# DAC_GainOutputStage2.net
KiCad netlist of a schematic drawn in EAGLE
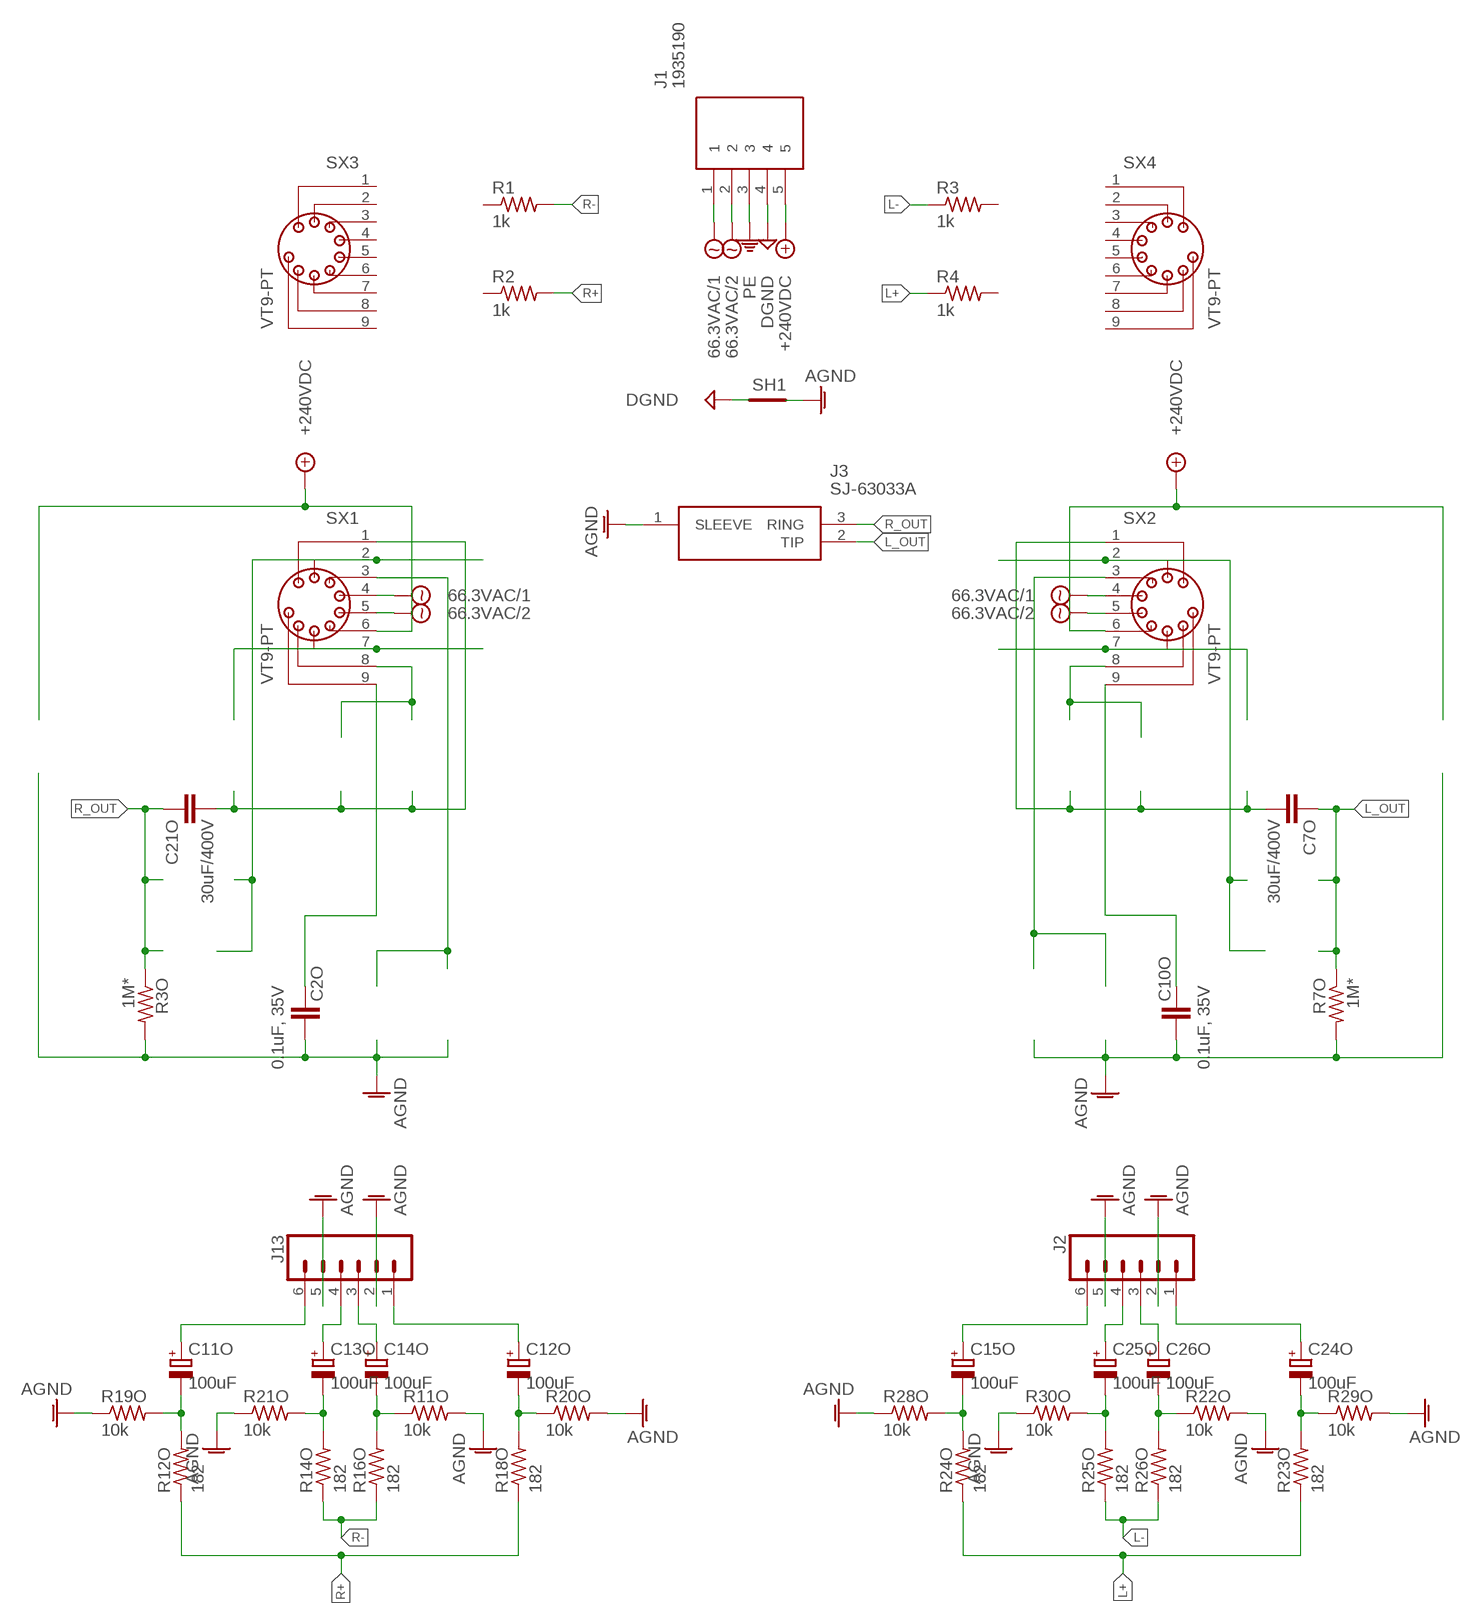
[diagram p0: schematic, sheet 1]

(export (version "E")
  (design (tool "Eeschema 10.0.6"))
  (components
    (comp (ref "C2O")
      (value "0.1uF, 35V")
      (footprint "eagle-import:MKS4B031002A00JC00")
      (fields
        (field (name "MANUFACTURER_PART_NUMBER") "MKS4B031002A00JC00")
        (field (name "MOUSER_PART_NUMBER") "505-MKS4B0312AJC")
      )
      (libsource (lib "eagle-import") (part "MKS4B031002A00JC00"))
    )
    (comp (ref "C7O")
      (value "30uF/400V")
      (footprint "eagle-import:DCP4G053006ID2KSSD")
      (fields
        (field (name "MANUFACTURER_PART_NUMBER") "DCP4G053006ID2KSSD")
        (field (name "MOUSER_PART_NUMBER") "505-DCP4G0536ID2KSSD")
      )
      (libsource (lib "eagle-import") (part "DCP4G053006ID2KSSD"))
    )
    (comp (ref "C10O")
      (value "0.1uF, 35V")
      (footprint "eagle-import:MKS4B031002A00JC00")
      (fields
        (field (name "MANUFACTURER_PART_NUMBER") "MKS4B031002A00JC00")
        (field (name "MOUSER_PART_NUMBER") "505-MKS4B0312AJC")
      )
      (libsource (lib "eagle-import") (part "MKS4B031002A00JC00"))
    )
    (comp (ref "C11O")
      (value "100uF")
      (footprint "eagle-import:CAPPRD350W60D825H1300")
      (fields
        (field (name "ARROW_PART_NUMBER") "UFW1H101MPD1TD")
        (field (name "MOUSER_PART_NUMBER") "647-UFW1H101MPD1TD")
      )
      (libsource (lib "eagle-import") (part "UFW1H101MPD1TD"))
    )
    (comp (ref "C12O")
      (value "100uF")
      (footprint "eagle-import:CAPPRD350W60D825H1300")
      (fields
        (field (name "ARROW_PART_NUMBER") "UFW1H101MPD1TD")
        (field (name "MOUSER_PART_NUMBER") "647-UFW1H101MPD1TD")
      )
      (libsource (lib "eagle-import") (part "UFW1H101MPD1TD"))
    )
    (comp (ref "C13O")
      (value "100uF")
      (footprint "eagle-import:CAPPRD350W60D825H1300")
      (fields
        (field (name "ARROW_PART_NUMBER") "UFW1H101MPD1TD")
        (field (name "MOUSER_PART_NUMBER") "647-UFW1H101MPD1TD")
      )
      (libsource (lib "eagle-import") (part "UFW1H101MPD1TD"))
    )
    (comp (ref "C14O")
      (value "100uF")
      (footprint "eagle-import:CAPPRD350W60D825H1300")
      (fields
        (field (name "ARROW_PART_NUMBER") "UFW1H101MPD1TD")
        (field (name "MOUSER_PART_NUMBER") "647-UFW1H101MPD1TD")
      )
      (libsource (lib "eagle-import") (part "UFW1H101MPD1TD"))
    )
    (comp (ref "C15O")
      (value "100uF")
      (footprint "eagle-import:CAPPRD350W60D825H1300")
      (fields
        (field (name "ARROW_PART_NUMBER") "UFW1H101MPD1TD")
        (field (name "MOUSER_PART_NUMBER") "647-UFW1H101MPD1TD")
      )
      (libsource (lib "eagle-import") (part "UFW1H101MPD1TD"))
    )
    (comp (ref "C21O")
      (value "30uF/400V")
      (footprint "eagle-import:DCP4G053006ID2KSSD")
      (fields
        (field (name "MANUFACTURER_PART_NUMBER") "DCP4G053006ID2KSSD")
        (field (name "MOUSER_PART_NUMBER") "505-DCP4G0536ID2KSSD")
      )
      (libsource (lib "eagle-import") (part "DCP4G053006ID2KSSD"))
    )
    (comp (ref "C24O")
      (value "100uF")
      (footprint "eagle-import:CAPPRD350W60D825H1300")
      (fields
        (field (name "ARROW_PART_NUMBER") "UFW1H101MPD1TD")
        (field (name "MOUSER_PART_NUMBER") "647-UFW1H101MPD1TD")
      )
      (libsource (lib "eagle-import") (part "UFW1H101MPD1TD"))
    )
    (comp (ref "C25O")
      (value "100uF")
      (footprint "eagle-import:CAPPRD350W60D825H1300")
      (fields
        (field (name "ARROW_PART_NUMBER") "UFW1H101MPD1TD")
        (field (name "MOUSER_PART_NUMBER") "647-UFW1H101MPD1TD")
      )
      (libsource (lib "eagle-import") (part "UFW1H101MPD1TD"))
    )
    (comp (ref "C26O")
      (value "100uF")
      (footprint "eagle-import:CAPPRD350W60D825H1300")
      (fields
        (field (name "ARROW_PART_NUMBER") "UFW1H101MPD1TD")
        (field (name "MOUSER_PART_NUMBER") "647-UFW1H101MPD1TD")
      )
      (libsource (lib "eagle-import") (part "UFW1H101MPD1TD"))
    )
    (comp (ref "J1")
      (value "1935190")
      (footprint "eagle-import:1935190")
      (fields (field (name "MOUSER_PART_NUMBER") "651-1935190"))
      (libsource (lib "eagle-import") (part "1935190"))
    )
    (comp (ref "J2")
      (value "CONN_06SILK_FEMALE_PTH")
      (footprint "eagle-import:1X06")
      (libsource (lib "eagle-import") (part "CONN_06SILK_FEMALE_PTH"))
    )
    (comp (ref "J3")
      (value "SJ-63033A")
      (footprint "eagle-import:SJ63033A")
      (libsource (lib "eagle-import") (part "SJ-63033A"))
    )
    (comp (ref "J13")
      (value "CONN_06SILK_FEMALE_PTH")
      (footprint "eagle-import:1X06")
      (libsource (lib "eagle-import") (part "CONN_06SILK_FEMALE_PTH"))
    )
    (comp (ref "R1")
      (value "1k")
      (footprint "eagle-import:0207_10")
      (libsource (lib "eagle-import") (part "R-US_0207/10"))
    )
    (comp (ref "R2")
      (value "1k")
      (footprint "eagle-import:0207_10")
      (libsource (lib "eagle-import") (part "R-US_0207/10"))
    )
    (comp (ref "R3")
      (value "1k")
      (footprint "eagle-import:0207_10")
      (libsource (lib "eagle-import") (part "R-US_0207/10"))
    )
    (comp (ref "R3O")
      (value "1M*")
      (footprint "eagle-import:RESAD1540W60L620D230")
      (fields
        (field (name "MANUFACTURER_PART_NUMBER") "LR1F1M0")
        (field (name "MOUSER_PART_NUMBER") "279-LR1F1M0")
      )
      (libsource (lib "eagle-import") (part "LR1F1M0"))
    )
    (comp (ref "R4")
      (value "1k")
      (footprint "eagle-import:0207_10")
      (libsource (lib "eagle-import") (part "R-US_0207/10"))
    )
    (comp (ref "R7O")
      (value "1M*")
      (footprint "eagle-import:RESAD1540W60L620D230")
      (fields
        (field (name "MANUFACTURER_PART_NUMBER") "LR1F1M0")
        (field (name "MOUSER_PART_NUMBER") "279-LR1F1M0")
      )
      (libsource (lib "eagle-import") (part "LR1F1M0"))
    )
    (comp (ref "R11O")
      (value "10k")
      (footprint "eagle-import:RESAD1540W55L620D230")
      (fields
        (field (name "MANUFACTURER_PART_NUMBER") "LR1F10K")
        (field (name "MOUSER_PART_NUMBER") "279-LR1F10K")
      )
      (libsource (lib "eagle-import") (part "LR1F10K"))
    )
    (comp (ref "R12O")
      (value "182")
      (footprint "eagle-import:RESAD1590W60L630D240")
      (fields (field (name "MANUFACTURER_PART_NUMBER") "MF0207FTE52-182R"))
      (libsource (lib "eagle-import") (part "MF0207FTE52-182R"))
    )
    (comp (ref "R14O")
      (value "182")
      (footprint "eagle-import:RESAD1590W60L630D240")
      (fields (field (name "MANUFACTURER_PART_NUMBER") "MF0207FTE52-182R"))
      (libsource (lib "eagle-import") (part "MF0207FTE52-182R"))
    )
    (comp (ref "R16O")
      (value "182")
      (footprint "eagle-import:RESAD1590W60L630D240")
      (fields (field (name "MANUFACTURER_PART_NUMBER") "MF0207FTE52-182R"))
      (libsource (lib "eagle-import") (part "MF0207FTE52-182R"))
    )
    (comp (ref "R18O")
      (value "182")
      (footprint "eagle-import:RESAD1590W60L630D240")
      (fields (field (name "MANUFACTURER_PART_NUMBER") "MF0207FTE52-182R"))
      (libsource (lib "eagle-import") (part "MF0207FTE52-182R"))
    )
    (comp (ref "R19O")
      (value "10k")
      (footprint "eagle-import:RESAD1540W55L620D230")
      (fields
        (field (name "MANUFACTURER_PART_NUMBER") "LR1F10K")
        (field (name "MOUSER_PART_NUMBER") "279-LR1F10K")
      )
      (libsource (lib "eagle-import") (part "LR1F10K"))
    )
    (comp (ref "R20O")
      (value "10k")
      (footprint "eagle-import:RESAD1540W55L620D230")
      (fields
        (field (name "MANUFACTURER_PART_NUMBER") "LR1F10K")
        (field (name "MOUSER_PART_NUMBER") "279-LR1F10K")
      )
      (libsource (lib "eagle-import") (part "LR1F10K"))
    )
    (comp (ref "R21O")
      (value "10k")
      (footprint "eagle-import:RESAD1540W55L620D230")
      (fields
        (field (name "MANUFACTURER_PART_NUMBER") "LR1F10K")
        (field (name "MOUSER_PART_NUMBER") "279-LR1F10K")
      )
      (libsource (lib "eagle-import") (part "LR1F10K"))
    )
    (comp (ref "R22O")
      (value "10k")
      (footprint "eagle-import:RESAD1540W55L620D230")
      (fields
        (field (name "MANUFACTURER_PART_NUMBER") "LR1F10K")
        (field (name "MOUSER_PART_NUMBER") "279-LR1F10K")
      )
      (libsource (lib "eagle-import") (part "LR1F10K"))
    )
    (comp (ref "R23O")
      (value "182")
      (footprint "eagle-import:RESAD1590W60L630D240")
      (fields (field (name "MANUFACTURER_PART_NUMBER") "MF0207FTE52-182R"))
      (libsource (lib "eagle-import") (part "MF0207FTE52-182R"))
    )
    (comp (ref "R24O")
      (value "182")
      (footprint "eagle-import:RESAD1590W60L630D240")
      (fields (field (name "MANUFACTURER_PART_NUMBER") "MF0207FTE52-182R"))
      (libsource (lib "eagle-import") (part "MF0207FTE52-182R"))
    )
    (comp (ref "R25O")
      (value "182")
      (footprint "eagle-import:RESAD1590W60L630D240")
      (fields (field (name "MANUFACTURER_PART_NUMBER") "MF0207FTE52-182R"))
      (libsource (lib "eagle-import") (part "MF0207FTE52-182R"))
    )
    (comp (ref "R26O")
      (value "182")
      (footprint "eagle-import:RESAD1590W60L630D240")
      (fields (field (name "MANUFACTURER_PART_NUMBER") "MF0207FTE52-182R"))
      (libsource (lib "eagle-import") (part "MF0207FTE52-182R"))
    )
    (comp (ref "R28O")
      (value "10k")
      (footprint "eagle-import:RESAD1540W55L620D230")
      (fields
        (field (name "MANUFACTURER_PART_NUMBER") "LR1F10K")
        (field (name "MOUSER_PART_NUMBER") "279-LR1F10K")
      )
      (libsource (lib "eagle-import") (part "LR1F10K"))
    )
    (comp (ref "R29O")
      (value "10k")
      (footprint "eagle-import:RESAD1540W55L620D230")
      (fields
        (field (name "MANUFACTURER_PART_NUMBER") "LR1F10K")
        (field (name "MOUSER_PART_NUMBER") "279-LR1F10K")
      )
      (libsource (lib "eagle-import") (part "LR1F10K"))
    )
    (comp (ref "R30O")
      (value "10k")
      (footprint "eagle-import:RESAD1540W55L620D230")
      (fields
        (field (name "MANUFACTURER_PART_NUMBER") "LR1F10K")
        (field (name "MOUSER_PART_NUMBER") "279-LR1F10K")
      )
      (libsource (lib "eagle-import") (part "LR1F10K"))
    )
    (comp (ref "SH1")
      (value "SHORTA5")
      (footprint "eagle-import:SHORT_ALL-50")
      (libsource (lib "eagle-import") (part "SHORTA5"))
    )
    (comp (ref "SX1")
      (value "VT9-PT")
      (footprint "eagle-import:VT9-PT")
      (libsource (lib "eagle-import") (part "VT9-PT"))
    )
    (comp (ref "SX2")
      (value "VT9-PT")
      (footprint "eagle-import:VT9-PT")
      (libsource (lib "eagle-import") (part "VT9-PT"))
    )
    (comp (ref "SX3")
      (value "VT9-PT")
      (footprint "eagle-import:VT9-PT")
      (libsource (lib "eagle-import") (part "VT9-PT"))
    )
    (comp (ref "SX4")
      (value "VT9-PT")
      (footprint "eagle-import:VT9-PT")
      (libsource (lib "eagle-import") (part "VT9-PT"))
    )
  )
  (nets
    (net (code "1") (name "+240VDC") (class "Default")
      (node (ref "J1") (pin "5") (pinfunction "5_5") (pintype "bidirectional"))
      (node (ref "SX1") (pin "6") (pinfunction "6_6") (pintype "passive"))
      (node (ref "SX2") (pin "6") (pinfunction "6_6") (pintype "passive"))
    )
    (net (code "2") (name "66.3VAC{slash}1") (class "Default")
      (node (ref "J1") (pin "1") (pinfunction "1_1") (pintype "bidirectional"))
      (node (ref "SX1") (pin "4") (pinfunction "4_4") (pintype "passive"))
      (node (ref "SX2") (pin "4") (pinfunction "4_4") (pintype "passive"))
    )
    (net (code "3") (name "66.3VAC{slash}2") (class "Default")
      (node (ref "J1") (pin "2") (pinfunction "2_2") (pintype "bidirectional"))
      (node (ref "SX1") (pin "5") (pinfunction "5_5") (pintype "passive"))
      (node (ref "SX2") (pin "5") (pinfunction "5_5") (pintype "passive"))
    )
    (net (code "4") (name "AGND") (class "Default")
      (node (ref "C10O") (pin "2") (pinfunction "2_2") (pintype "passive"))
      (node (ref "C2O") (pin "2") (pinfunction "2_2") (pintype "passive"))
      (node (ref "J13") (pin "2") (pinfunction "2_2") (pintype "passive"))
      (node (ref "J13") (pin "5") (pinfunction "5_5") (pintype "passive"))
      (node (ref "J2") (pin "2") (pinfunction "2_2") (pintype "passive"))
      (node (ref "J2") (pin "5") (pinfunction "5_5") (pintype "passive"))
      (node (ref "J3") (pin "1") (pinfunction "SLEEVE_1") (pintype "bidirectional"))
      (node (ref "R11O") (pin "2") (pinfunction "2_2") (pintype "passive"))
      (node (ref "R19O") (pin "1") (pinfunction "1_1") (pintype "passive"))
      (node (ref "R20O") (pin "2") (pinfunction "2_2") (pintype "passive"))
      (node (ref "R21O") (pin "1") (pinfunction "1_1") (pintype "passive"))
      (node (ref "R22O") (pin "2") (pinfunction "2_2") (pintype "passive"))
      (node (ref "R28O") (pin "1") (pinfunction "1_1") (pintype "passive"))
      (node (ref "R29O") (pin "2") (pinfunction "2_2") (pintype "passive"))
      (node (ref "R30O") (pin "1") (pinfunction "1_1") (pintype "passive"))
      (node (ref "R3O") (pin "2") (pinfunction "2_2") (pintype "passive"))
      (node (ref "R7O") (pin "2") (pinfunction "2_2") (pintype "passive"))
      (node (ref "SH1") (pin "2") (pinfunction "P$2_2") (pintype "bidirectional"))
    )
    (net (code "5") (name "DGND") (class "Default")
      (node (ref "J1") (pin "4") (pinfunction "4_4") (pintype "bidirectional"))
      (node (ref "SH1") (pin "1") (pinfunction "P$1_1") (pintype "bidirectional"))
    )
    (net (code "6") (name "L+") (class "Default")
      (node (ref "R23O") (pin "1") (pinfunction "1_1") (pintype "passive"))
      (node (ref "R24O") (pin "1") (pinfunction "1_1") (pintype "passive"))
      (node (ref "R4") (pin "1") (pinfunction "1_1") (pintype "passive"))
    )
    (net (code "7") (name "L-") (class "Default")
      (node (ref "R25O") (pin "1") (pinfunction "1_1") (pintype "passive"))
      (node (ref "R26O") (pin "1") (pinfunction "1_1") (pintype "passive"))
      (node (ref "R3") (pin "1") (pinfunction "1_1") (pintype "passive"))
    )
    (net (code "8") (name "L_OUT") (class "Default")
      (node (ref "C7O") (pin "1") (pinfunction "1_1") (pintype "passive"))
      (node (ref "J3") (pin "2") (pinfunction "TIP_2") (pintype "bidirectional"))
      (node (ref "R7O") (pin "1") (pinfunction "1_1") (pintype "passive"))
    )
    (net (code "9") (name "Net-(C2O-Pad1)") (class "Default")
      (node (ref "C2O") (pin "1") (pinfunction "1_1") (pintype "passive"))
      (node (ref "SX1") (pin "9") (pinfunction "9_9") (pintype "passive"))
    )
    (net (code "10") (name "Net-(C7O-Pad2)") (class "Default")
      (node (ref "C7O") (pin "2") (pinfunction "2_2") (pintype "passive"))
      (node (ref "SX2") (pin "1") (pinfunction "1_1") (pintype "passive"))
    )
    (net (code "11") (name "Net-(C10O-Pad1)") (class "Default")
      (node (ref "C10O") (pin "1") (pinfunction "1_1") (pintype "passive"))
      (node (ref "SX2") (pin "9") (pinfunction "9_9") (pintype "passive"))
    )
    (net (code "12") (name "Net-(C11O-+)") (class "Default")
      (node (ref "C11O") (pin "1") (pinfunction "+_1") (pintype "passive"))
      (node (ref "J13") (pin "6") (pinfunction "6_6") (pintype "passive"))
    )
    (net (code "13") (name "Net-(C11O--)") (class "Default")
      (node (ref "C11O") (pin "2") (pinfunction "-_2") (pintype "passive"))
      (node (ref "R12O") (pin "2") (pinfunction "2_2") (pintype "passive"))
      (node (ref "R19O") (pin "2") (pinfunction "2_2") (pintype "passive"))
    )
    (net (code "14") (name "Net-(C12O-+)") (class "Default")
      (node (ref "C12O") (pin "1") (pinfunction "+_1") (pintype "passive"))
      (node (ref "J13") (pin "1") (pinfunction "1_1") (pintype "passive"))
    )
    (net (code "15") (name "Net-(C12O--)") (class "Default")
      (node (ref "C12O") (pin "2") (pinfunction "-_2") (pintype "passive"))
      (node (ref "R18O") (pin "2") (pinfunction "2_2") (pintype "passive"))
      (node (ref "R20O") (pin "1") (pinfunction "1_1") (pintype "passive"))
    )
    (net (code "16") (name "Net-(C13O-+)") (class "Default")
      (node (ref "C13O") (pin "1") (pinfunction "+_1") (pintype "passive"))
      (node (ref "J13") (pin "4") (pinfunction "4_4") (pintype "passive"))
    )
    (net (code "17") (name "Net-(C13O--)") (class "Default")
      (node (ref "C13O") (pin "2") (pinfunction "-_2") (pintype "passive"))
      (node (ref "R14O") (pin "2") (pinfunction "2_2") (pintype "passive"))
      (node (ref "R21O") (pin "2") (pinfunction "2_2") (pintype "passive"))
    )
    (net (code "18") (name "Net-(C14O-+)") (class "Default")
      (node (ref "C14O") (pin "1") (pinfunction "+_1") (pintype "passive"))
      (node (ref "J13") (pin "3") (pinfunction "3_3") (pintype "passive"))
    )
    (net (code "19") (name "Net-(C14O--)") (class "Default")
      (node (ref "C14O") (pin "2") (pinfunction "-_2") (pintype "passive"))
      (node (ref "R11O") (pin "1") (pinfunction "1_1") (pintype "passive"))
      (node (ref "R16O") (pin "2") (pinfunction "2_2") (pintype "passive"))
    )
    (net (code "20") (name "Net-(C15O-+)") (class "Default")
      (node (ref "C15O") (pin "1") (pinfunction "+_1") (pintype "passive"))
      (node (ref "J2") (pin "6") (pinfunction "6_6") (pintype "passive"))
    )
    (net (code "21") (name "Net-(C15O--)") (class "Default")
      (node (ref "C15O") (pin "2") (pinfunction "-_2") (pintype "passive"))
      (node (ref "R24O") (pin "2") (pinfunction "2_2") (pintype "passive"))
      (node (ref "R28O") (pin "2") (pinfunction "2_2") (pintype "passive"))
    )
    (net (code "22") (name "Net-(C21O-Pad2)") (class "Default")
      (node (ref "C21O") (pin "2") (pinfunction "2_2") (pintype "passive"))
      (node (ref "SX1") (pin "1") (pinfunction "1_1") (pintype "passive"))
    )
    (net (code "23") (name "Net-(C24O-+)") (class "Default")
      (node (ref "C24O") (pin "1") (pinfunction "+_1") (pintype "passive"))
      (node (ref "J2") (pin "1") (pinfunction "1_1") (pintype "passive"))
    )
    (net (code "24") (name "Net-(C24O--)") (class "Default")
      (node (ref "C24O") (pin "2") (pinfunction "-_2") (pintype "passive"))
      (node (ref "R23O") (pin "2") (pinfunction "2_2") (pintype "passive"))
      (node (ref "R29O") (pin "1") (pinfunction "1_1") (pintype "passive"))
    )
    (net (code "25") (name "Net-(C25O-+)") (class "Default")
      (node (ref "C25O") (pin "1") (pinfunction "+_1") (pintype "passive"))
      (node (ref "J2") (pin "4") (pinfunction "4_4") (pintype "passive"))
    )
    (net (code "26") (name "Net-(C25O--)") (class "Default")
      (node (ref "C25O") (pin "2") (pinfunction "-_2") (pintype "passive"))
      (node (ref "R25O") (pin "2") (pinfunction "2_2") (pintype "passive"))
      (node (ref "R30O") (pin "2") (pinfunction "2_2") (pintype "passive"))
    )
    (net (code "27") (name "Net-(C26O-+)") (class "Default")
      (node (ref "C26O") (pin "1") (pinfunction "+_1") (pintype "passive"))
      (node (ref "J2") (pin "3") (pinfunction "3_3") (pintype "passive"))
    )
    (net (code "28") (name "Net-(C26O--)") (class "Default")
      (node (ref "C26O") (pin "2") (pinfunction "-_2") (pintype "passive"))
      (node (ref "R22O") (pin "1") (pinfunction "1_1") (pintype "passive"))
      (node (ref "R26O") (pin "2") (pinfunction "2_2") (pintype "passive"))
    )
    (net (code "29") (name "PE") (class "Default")
      (node (ref "J1") (pin "3") (pinfunction "3_3") (pintype "bidirectional"))
    )
    (net (code "30") (name "R+") (class "Default")
      (node (ref "R12O") (pin "1") (pinfunction "1_1") (pintype "passive"))
      (node (ref "R18O") (pin "1") (pinfunction "1_1") (pintype "passive"))
      (node (ref "R2") (pin "2") (pinfunction "2_2") (pintype "passive"))
    )
    (net (code "31") (name "R-") (class "Default")
      (node (ref "R1") (pin "2") (pinfunction "2_2") (pintype "passive"))
      (node (ref "R14O") (pin "1") (pinfunction "1_1") (pintype "passive"))
      (node (ref "R16O") (pin "1") (pinfunction "1_1") (pintype "passive"))
    )
    (net (code "32") (name "R_OUT") (class "Default")
      (node (ref "C21O") (pin "1") (pinfunction "1_1") (pintype "passive"))
      (node (ref "J3") (pin "3") (pinfunction "RING_3") (pintype "bidirectional"))
      (node (ref "R3O") (pin "1") (pinfunction "1_1") (pintype "passive"))
    )
    (net (code "33") (name "unconnected-(R1-Pad1)") (class "Default")
      (node (ref "R1") (pin "1") (pinfunction "1_1") (pintype "passive"))
    )
    (net (code "34") (name "unconnected-(R2-Pad1)") (class "Default")
      (node (ref "R2") (pin "1") (pinfunction "1_1") (pintype "passive"))
    )
    (net (code "35") (name "unconnected-(R3-Pad2)") (class "Default")
      (node (ref "R3") (pin "2") (pinfunction "2_2") (pintype "passive"))
    )
    (net (code "36") (name "unconnected-(R4-Pad2)") (class "Default")
      (node (ref "R4") (pin "2") (pinfunction "2_2") (pintype "passive"))
    )
    (net (code "37") (name "unconnected-(SX1-Pad2)") (class "Default")
      (node (ref "SX1") (pin "2") (pinfunction "2_2") (pintype "passive"))
    )
    (net (code "38") (name "unconnected-(SX1-Pad3)") (class "Default")
      (node (ref "SX1") (pin "3") (pinfunction "3_3") (pintype "passive"))
    )
    (net (code "39") (name "unconnected-(SX1-Pad7)") (class "Default")
      (node (ref "SX1") (pin "7") (pinfunction "7_7") (pintype "passive"))
    )
    (net (code "40") (name "unconnected-(SX1-Pad8)") (class "Default")
      (node (ref "SX1") (pin "8") (pinfunction "8_8") (pintype "passive"))
    )
    (net (code "41") (name "unconnected-(SX2-Pad2)") (class "Default")
      (node (ref "SX2") (pin "2") (pinfunction "2_2") (pintype "passive"))
    )
    (net (code "42") (name "unconnected-(SX2-Pad3)") (class "Default")
      (node (ref "SX2") (pin "3") (pinfunction "3_3") (pintype "passive"))
    )
    (net (code "43") (name "unconnected-(SX2-Pad7)") (class "Default")
      (node (ref "SX2") (pin "7") (pinfunction "7_7") (pintype "passive"))
    )
    (net (code "44") (name "unconnected-(SX2-Pad8)") (class "Default")
      (node (ref "SX2") (pin "8") (pinfunction "8_8") (pintype "passive"))
    )
    (net (code "45") (name "unconnected-(SX3-Pad1)") (class "Default")
      (node (ref "SX3") (pin "1") (pinfunction "1_1") (pintype "passive"))
    )
    (net (code "46") (name "unconnected-(SX3-Pad2)") (class "Default")
      (node (ref "SX3") (pin "2") (pinfunction "2_2") (pintype "passive"))
    )
    (net (code "47") (name "unconnected-(SX3-Pad3)") (class "Default")
      (node (ref "SX3") (pin "3") (pinfunction "3_3") (pintype "passive"))
    )
    (net (code "48") (name "unconnected-(SX3-Pad4)") (class "Default")
      (node (ref "SX3") (pin "4") (pinfunction "4_4") (pintype "passive"))
    )
    (net (code "49") (name "unconnected-(SX3-Pad5)") (class "Default")
      (node (ref "SX3") (pin "5") (pinfunction "5_5") (pintype "passive"))
    )
    (net (code "50") (name "unconnected-(SX3-Pad6)") (class "Default")
      (node (ref "SX3") (pin "6") (pinfunction "6_6") (pintype "passive"))
    )
    (net (code "51") (name "unconnected-(SX3-Pad7)") (class "Default")
      (node (ref "SX3") (pin "7") (pinfunction "7_7") (pintype "passive"))
    )
    (net (code "52") (name "unconnected-(SX3-Pad8)") (class "Default")
      (node (ref "SX3") (pin "8") (pinfunction "8_8") (pintype "passive"))
    )
    (net (code "53") (name "unconnected-(SX3-Pad9)") (class "Default")
      (node (ref "SX3") (pin "9") (pinfunction "9_9") (pintype "passive"))
    )
    (net (code "54") (name "unconnected-(SX4-Pad1)") (class "Default")
      (node (ref "SX4") (pin "1") (pinfunction "1_1") (pintype "passive"))
    )
    (net (code "55") (name "unconnected-(SX4-Pad2)") (class "Default")
      (node (ref "SX4") (pin "2") (pinfunction "2_2") (pintype "passive"))
    )
    (net (code "56") (name "unconnected-(SX4-Pad3)") (class "Default")
      (node (ref "SX4") (pin "3") (pinfunction "3_3") (pintype "passive"))
    )
    (net (code "57") (name "unconnected-(SX4-Pad4)") (class "Default")
      (node (ref "SX4") (pin "4") (pinfunction "4_4") (pintype "passive"))
    )
    (net (code "58") (name "unconnected-(SX4-Pad5)") (class "Default")
      (node (ref "SX4") (pin "5") (pinfunction "5_5") (pintype "passive"))
    )
    (net (code "59") (name "unconnected-(SX4-Pad6)") (class "Default")
      (node (ref "SX4") (pin "6") (pinfunction "6_6") (pintype "passive"))
    )
    (net (code "60") (name "unconnected-(SX4-Pad7)") (class "Default")
      (node (ref "SX4") (pin "7") (pinfunction "7_7") (pintype "passive"))
    )
    (net (code "61") (name "unconnected-(SX4-Pad8)") (class "Default")
      (node (ref "SX4") (pin "8") (pinfunction "8_8") (pintype "passive"))
    )
    (net (code "62") (name "unconnected-(SX4-Pad9)") (class "Default")
      (node (ref "SX4") (pin "9") (pinfunction "9_9") (pintype "passive"))
    )
  )
)
